# schematic.net
KiCad netlist of a schematic drawn in EasyEDA
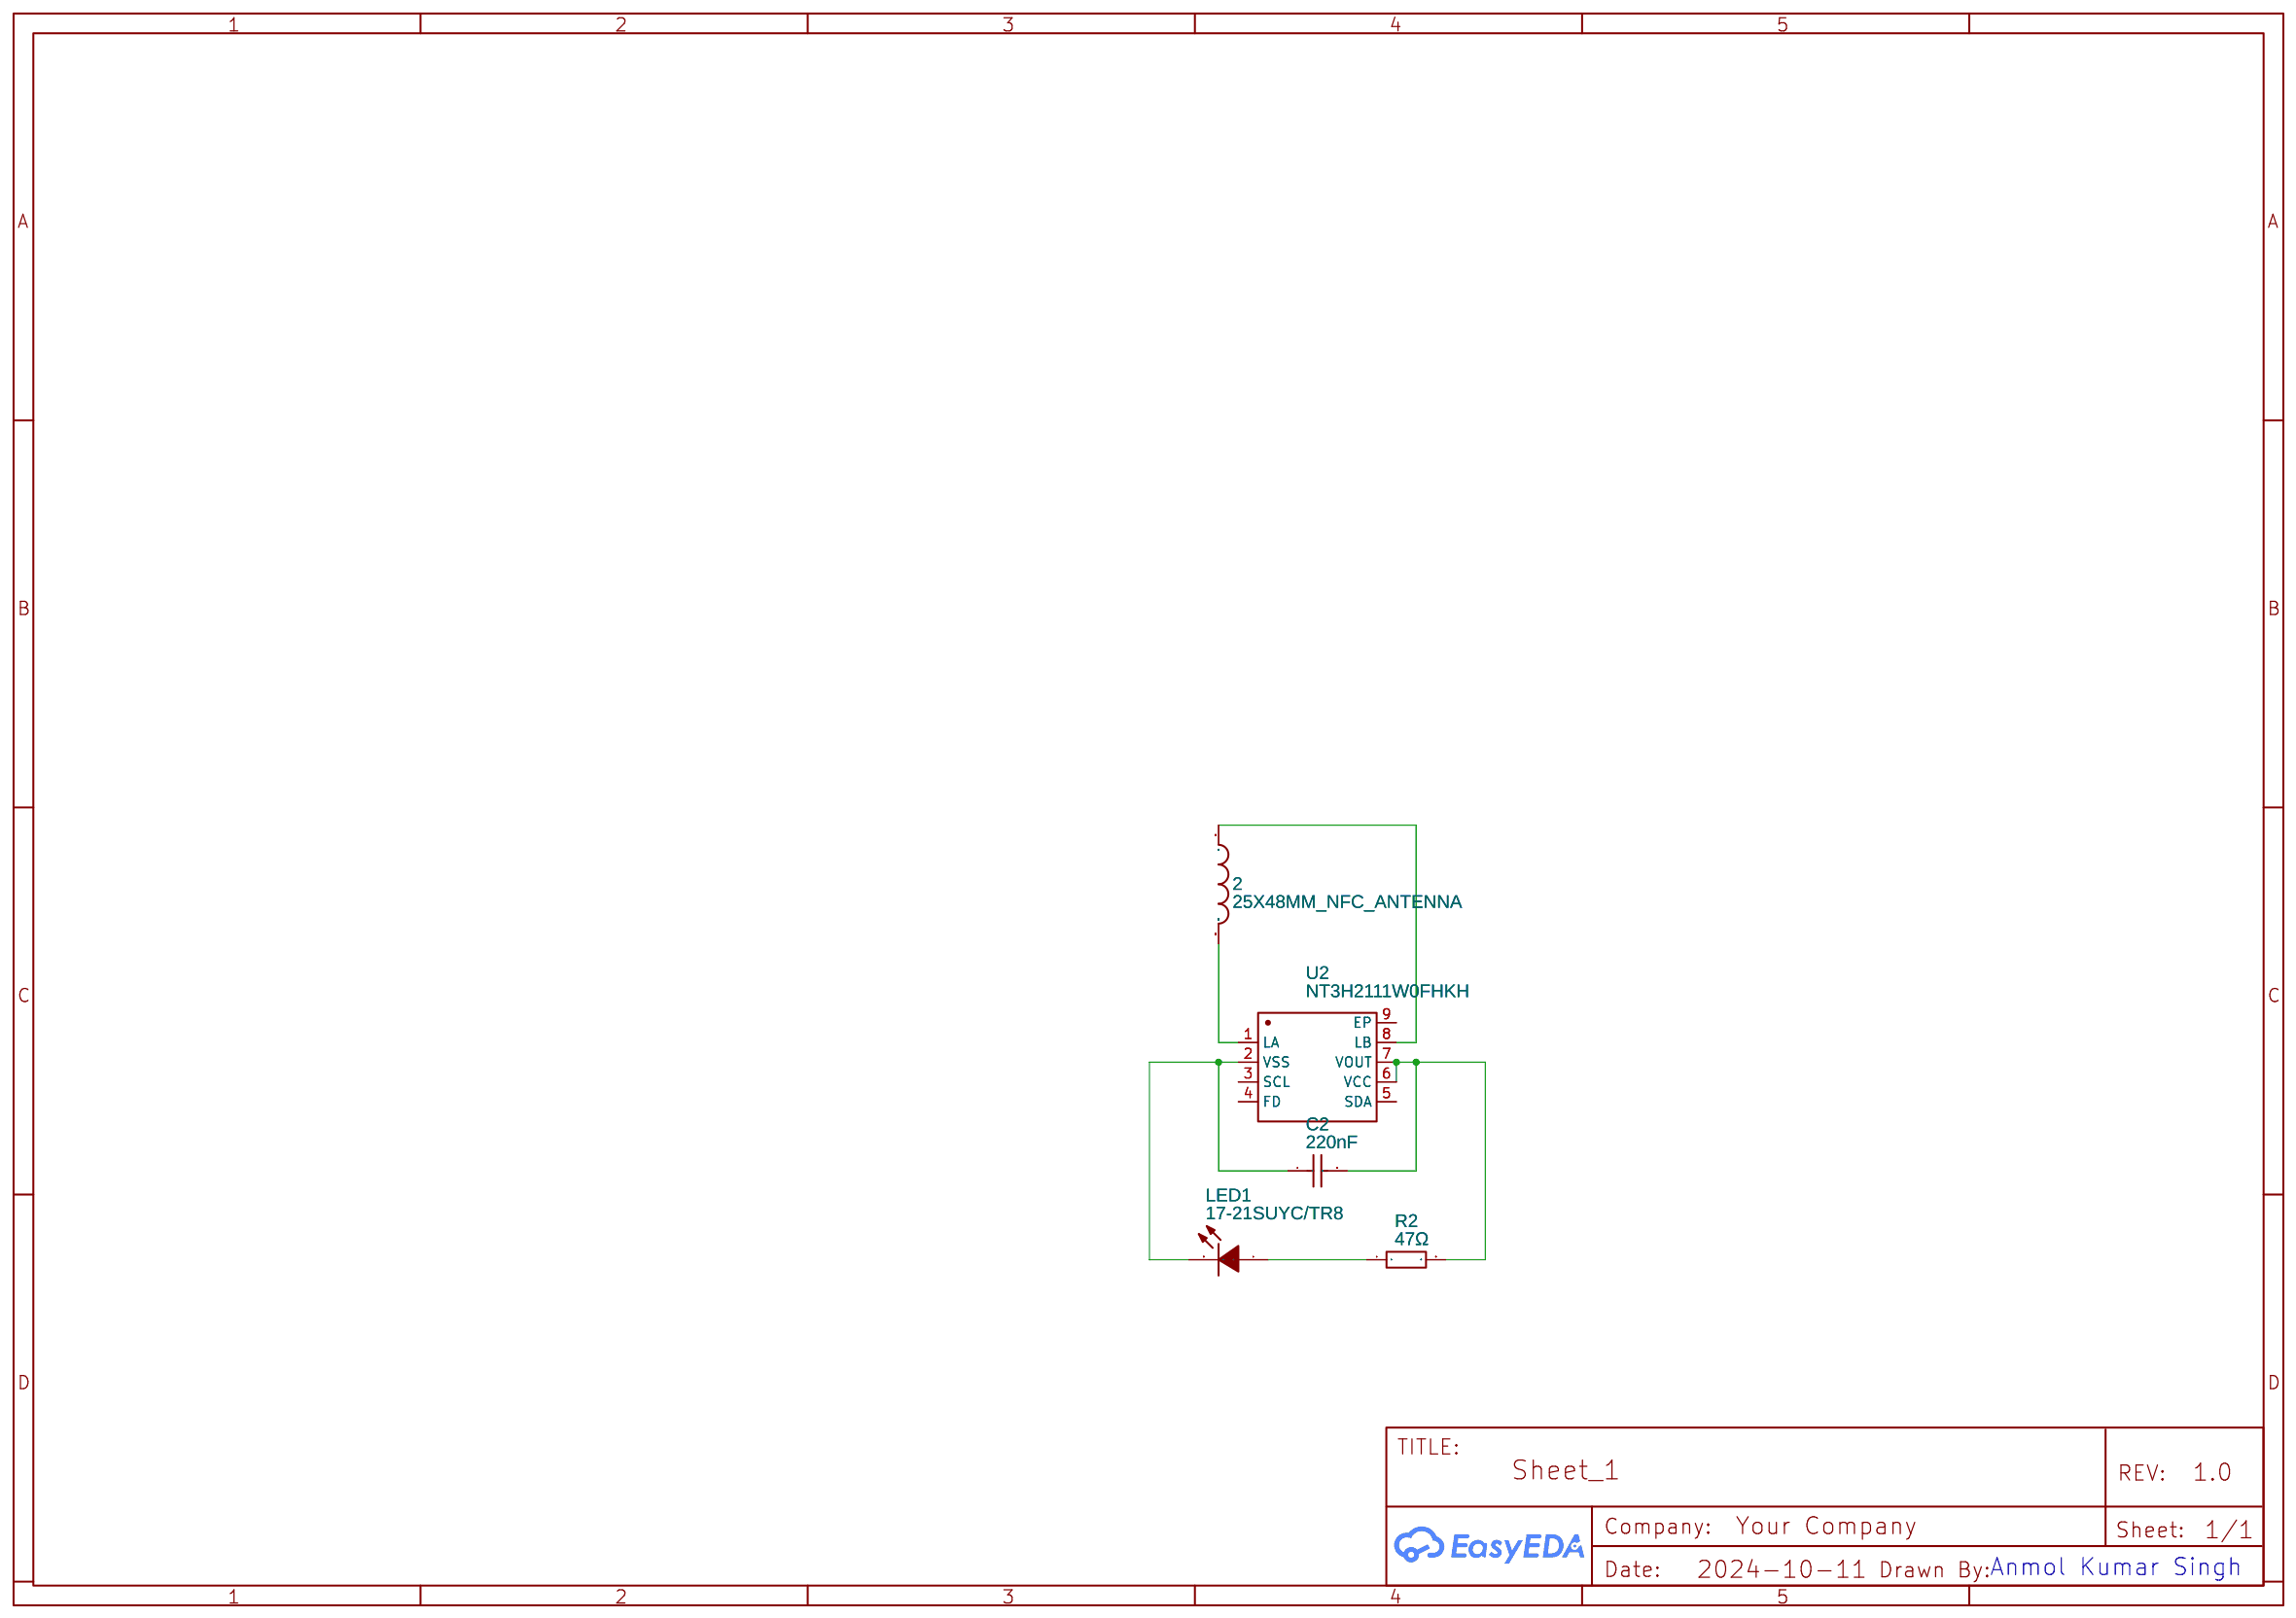
[diagram p0: schematic sheet]

(export (version "E")
  (design (tool "Eeschema 10.0.6"))
  (components
    (comp (ref "2") (value "25X48MM_NFC_ANTENNA") (libsource (lib "") (part "25X48MM_NFC_ANTENNA")))
    (comp (ref "C2")
      (value "220nF")
      (fields
        (field (name "Manufacturer Part") "CL10B224KA8NNNC")
        (field (name "Manufacturer") "SAMSUNG(三星)")
      )
      (libsource (lib "") (part "CL10B224KA8NNNC"))
    )
    (comp (ref "LED1")
      (value "17-21SUYC/TR8")
      (fields (field (name "Manufacturer Part") "KT-0805黄灯") (field (name "Manufacturer") "KENTO"))
      (libsource (lib "") (part "17-21SUYC/TR8"))
    )
    (comp (ref "R2")
      (value "47Ω")
      (fields
        (field (name "Manufacturer Part") "0603WAF470JT5E")
        (field (name "Manufacturer") "UNI-ROYAL(厚声)")
      )
      (libsource (lib "") (part "0603WAF470JT5E"))
    )
    (comp (ref "U2")
      (value "NT3H2111W0FHKH")
      (fields (field (name "Manufacturer") "NXP(恩智浦)"))
      (libsource (lib "") (part "NT3H2111W0FHKH"))
    )
  )
  (nets
    (net (code "1") (name "Net-(LED1-+)") (class "Default")
      (node (ref "LED1") (pin "1") (pinfunction "+_1") (pintype "unspecified"))
      (node (ref "R2") (pin "1") (pinfunction "1_1") (pintype "input"))
    )
    (net (code "2") (name "Net-(LED1--)") (class "Default")
      (node (ref "C2") (pin "1") (pinfunction "1_1") (pintype "input"))
      (node (ref "LED1") (pin "2") (pinfunction "-_2") (pintype "unspecified"))
      (node (ref "U2") (pin "2") (pinfunction "VSS_2") (pintype "unspecified"))
    )
    (net (code "3") (name "Net-(U2-LA)") (class "Default")
      (node (ref "2") (pin "P$2") (pinfunction "P$2_P$2") (pintype "bidirectional"))
      (node (ref "U2") (pin "1") (pinfunction "LA_1") (pintype "unspecified"))
    )
    (net (code "4") (name "Net-(U2-LB)") (class "Default")
      (node (ref "2") (pin "P$1") (pinfunction "P$1_P$1") (pintype "bidirectional"))
      (node (ref "U2") (pin "8") (pinfunction "LB_8") (pintype "unspecified"))
    )
    (net (code "5") (name "Net-(U2-VCC)") (class "Default")
      (node (ref "C2") (pin "2") (pinfunction "2_2") (pintype "input"))
      (node (ref "R2") (pin "2") (pinfunction "2_2") (pintype "input"))
      (node (ref "U2") (pin "6") (pinfunction "VCC_6") (pintype "unspecified"))
      (node (ref "U2") (pin "7") (pinfunction "VOUT_7") (pintype "unspecified"))
    )
    (net (code "6") (name "unconnected-(U2-EP-Pad9)") (class "Default")
      (node (ref "U2") (pin "9") (pinfunction "EP_9") (pintype "unspecified"))
    )
    (net (code "7") (name "unconnected-(U2-FD-Pad4)") (class "Default")
      (node (ref "U2") (pin "4") (pinfunction "FD_4") (pintype "unspecified"))
    )
    (net (code "8") (name "unconnected-(U2-SCL-Pad3)") (class "Default")
      (node (ref "U2") (pin "3") (pinfunction "SCL_3") (pintype "unspecified"))
    )
    (net (code "9") (name "unconnected-(U2-SDA-Pad5)") (class "Default")
      (node (ref "U2") (pin "5") (pinfunction "SDA_5") (pintype "unspecified"))
    )
  )
)
